# princessPhone.net
KiCad netlist of a schematic drawn in EAGLE
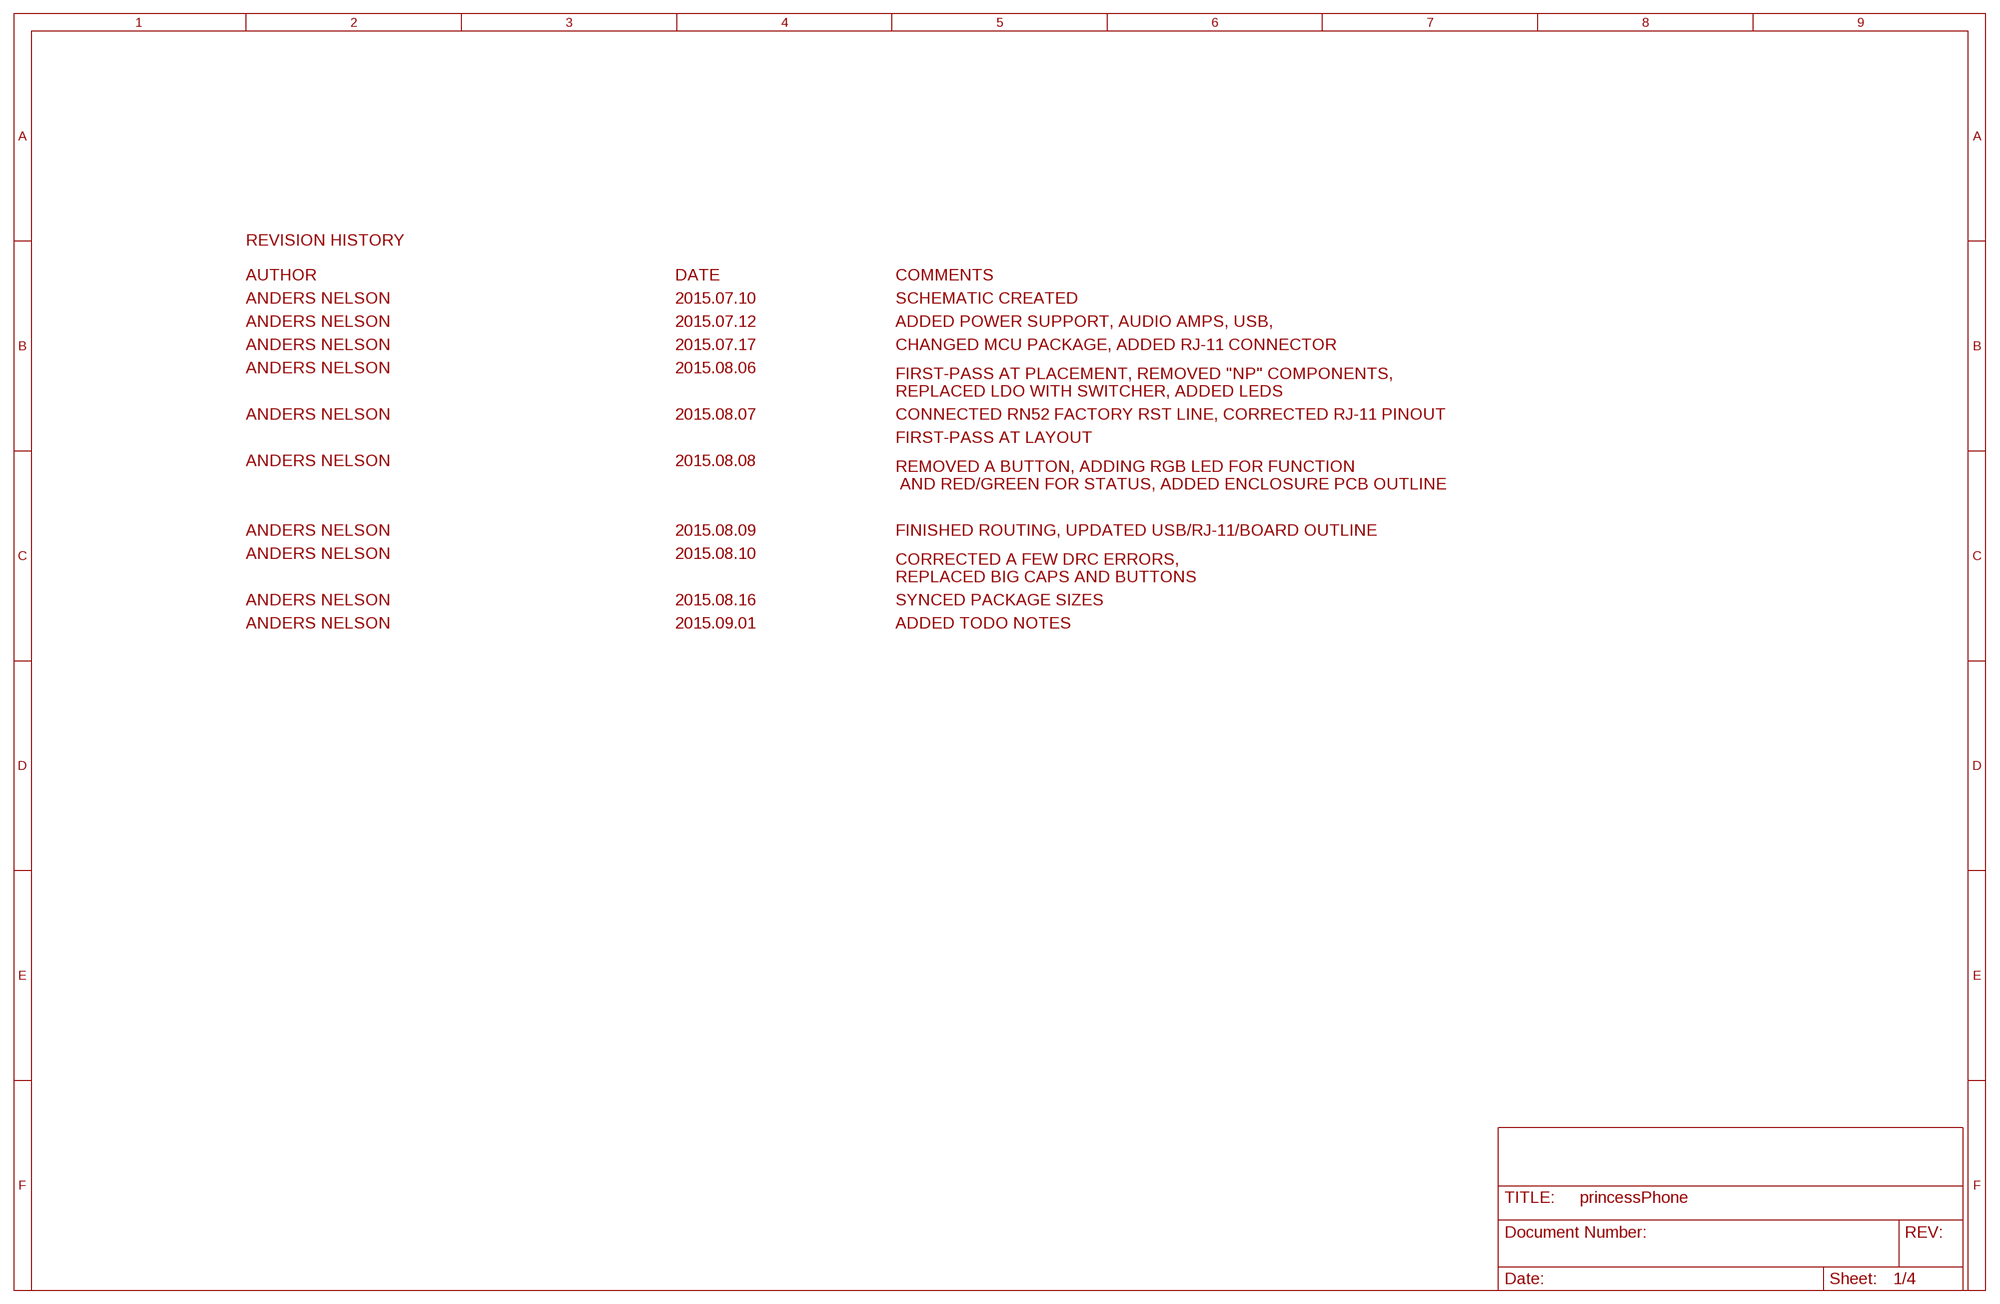
[diagram p0: schematic, sheet 1]
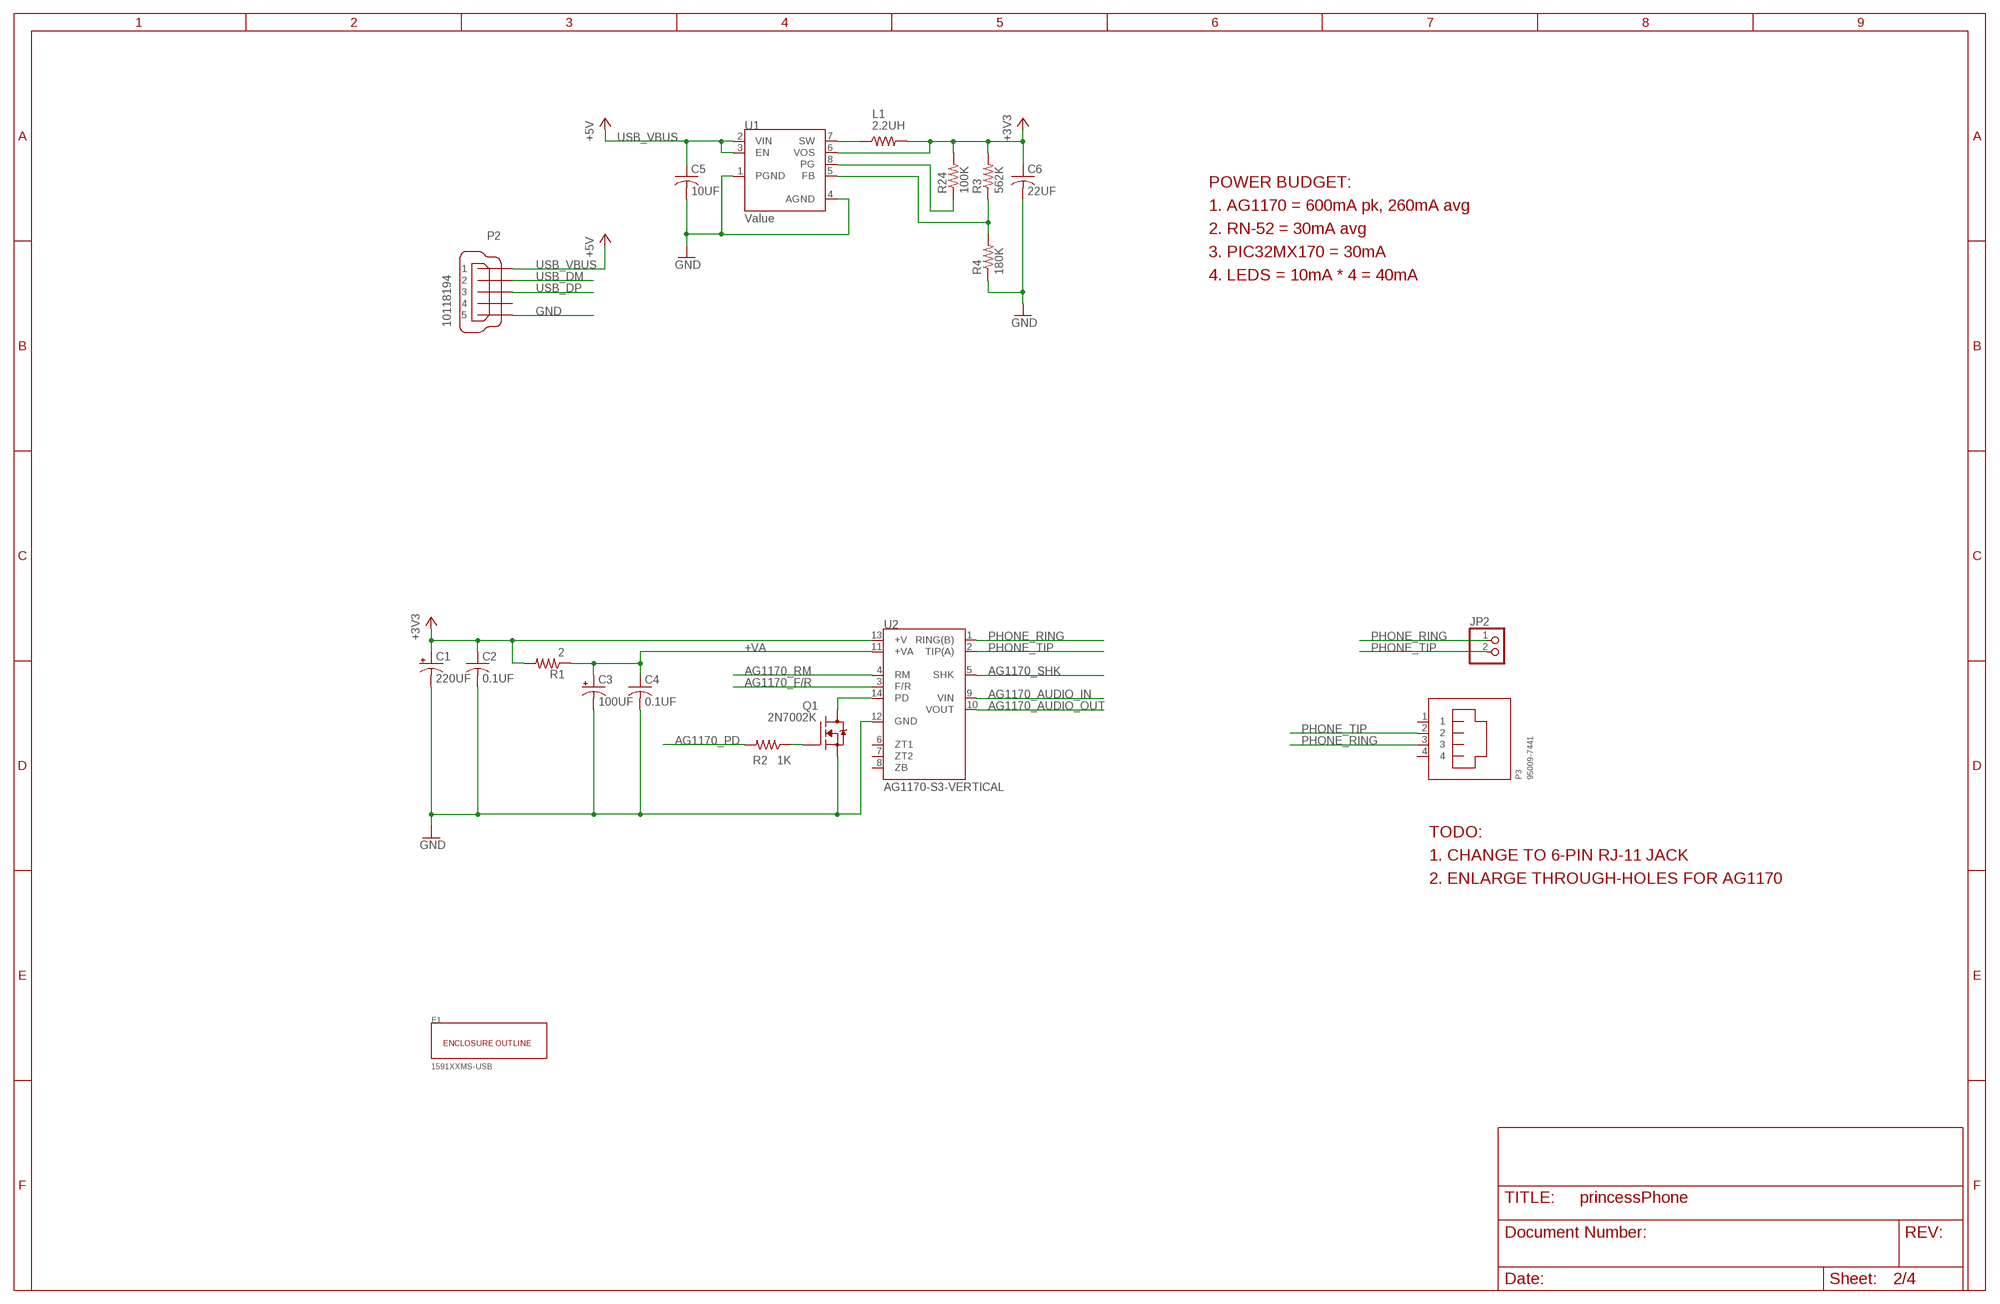
[diagram p1: schematic, sheet 2]
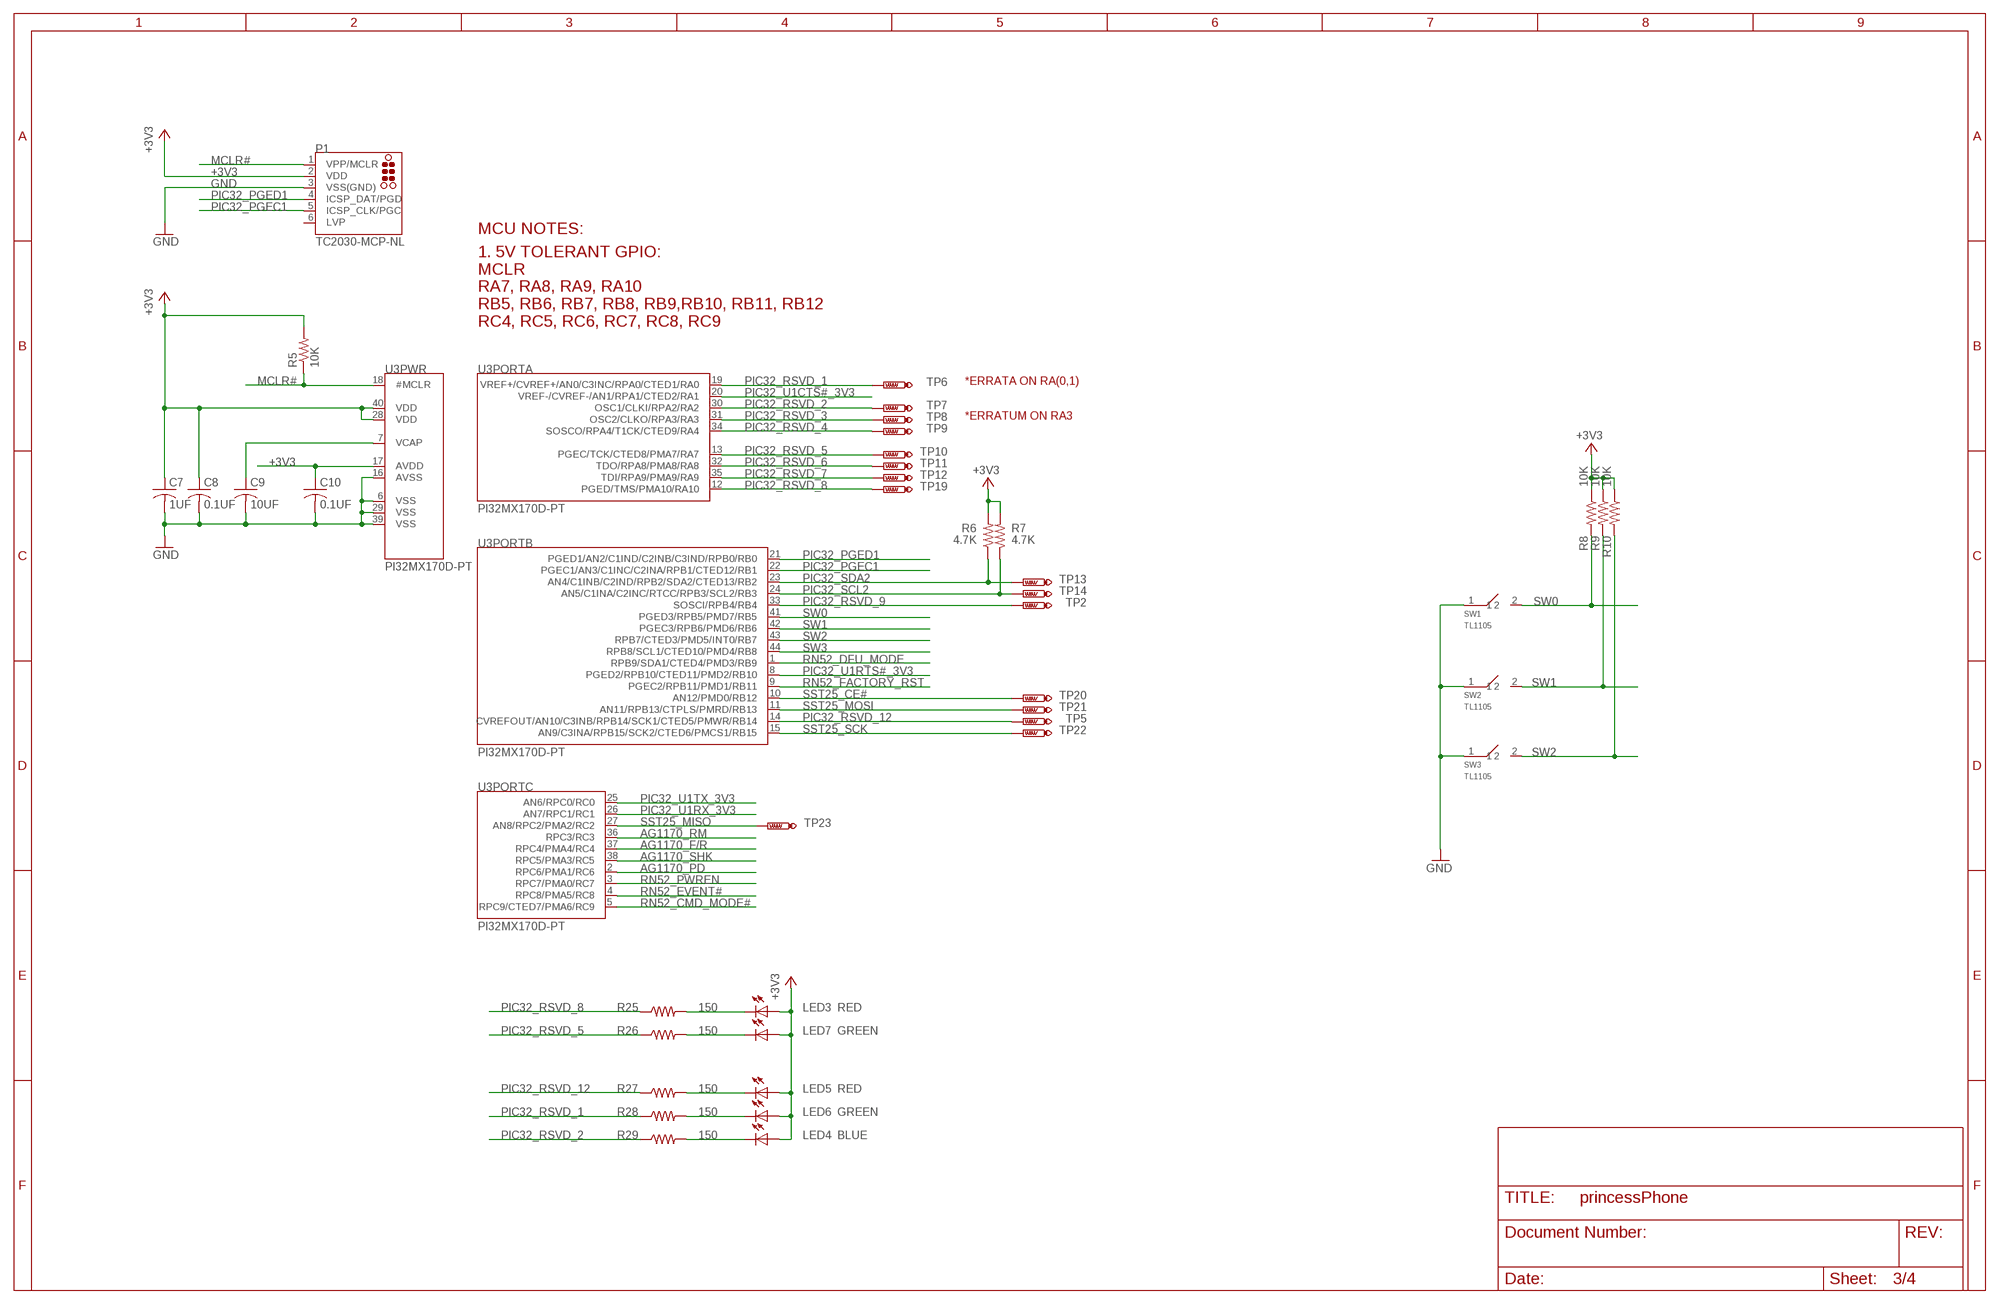
[diagram p2: schematic, sheet 3]
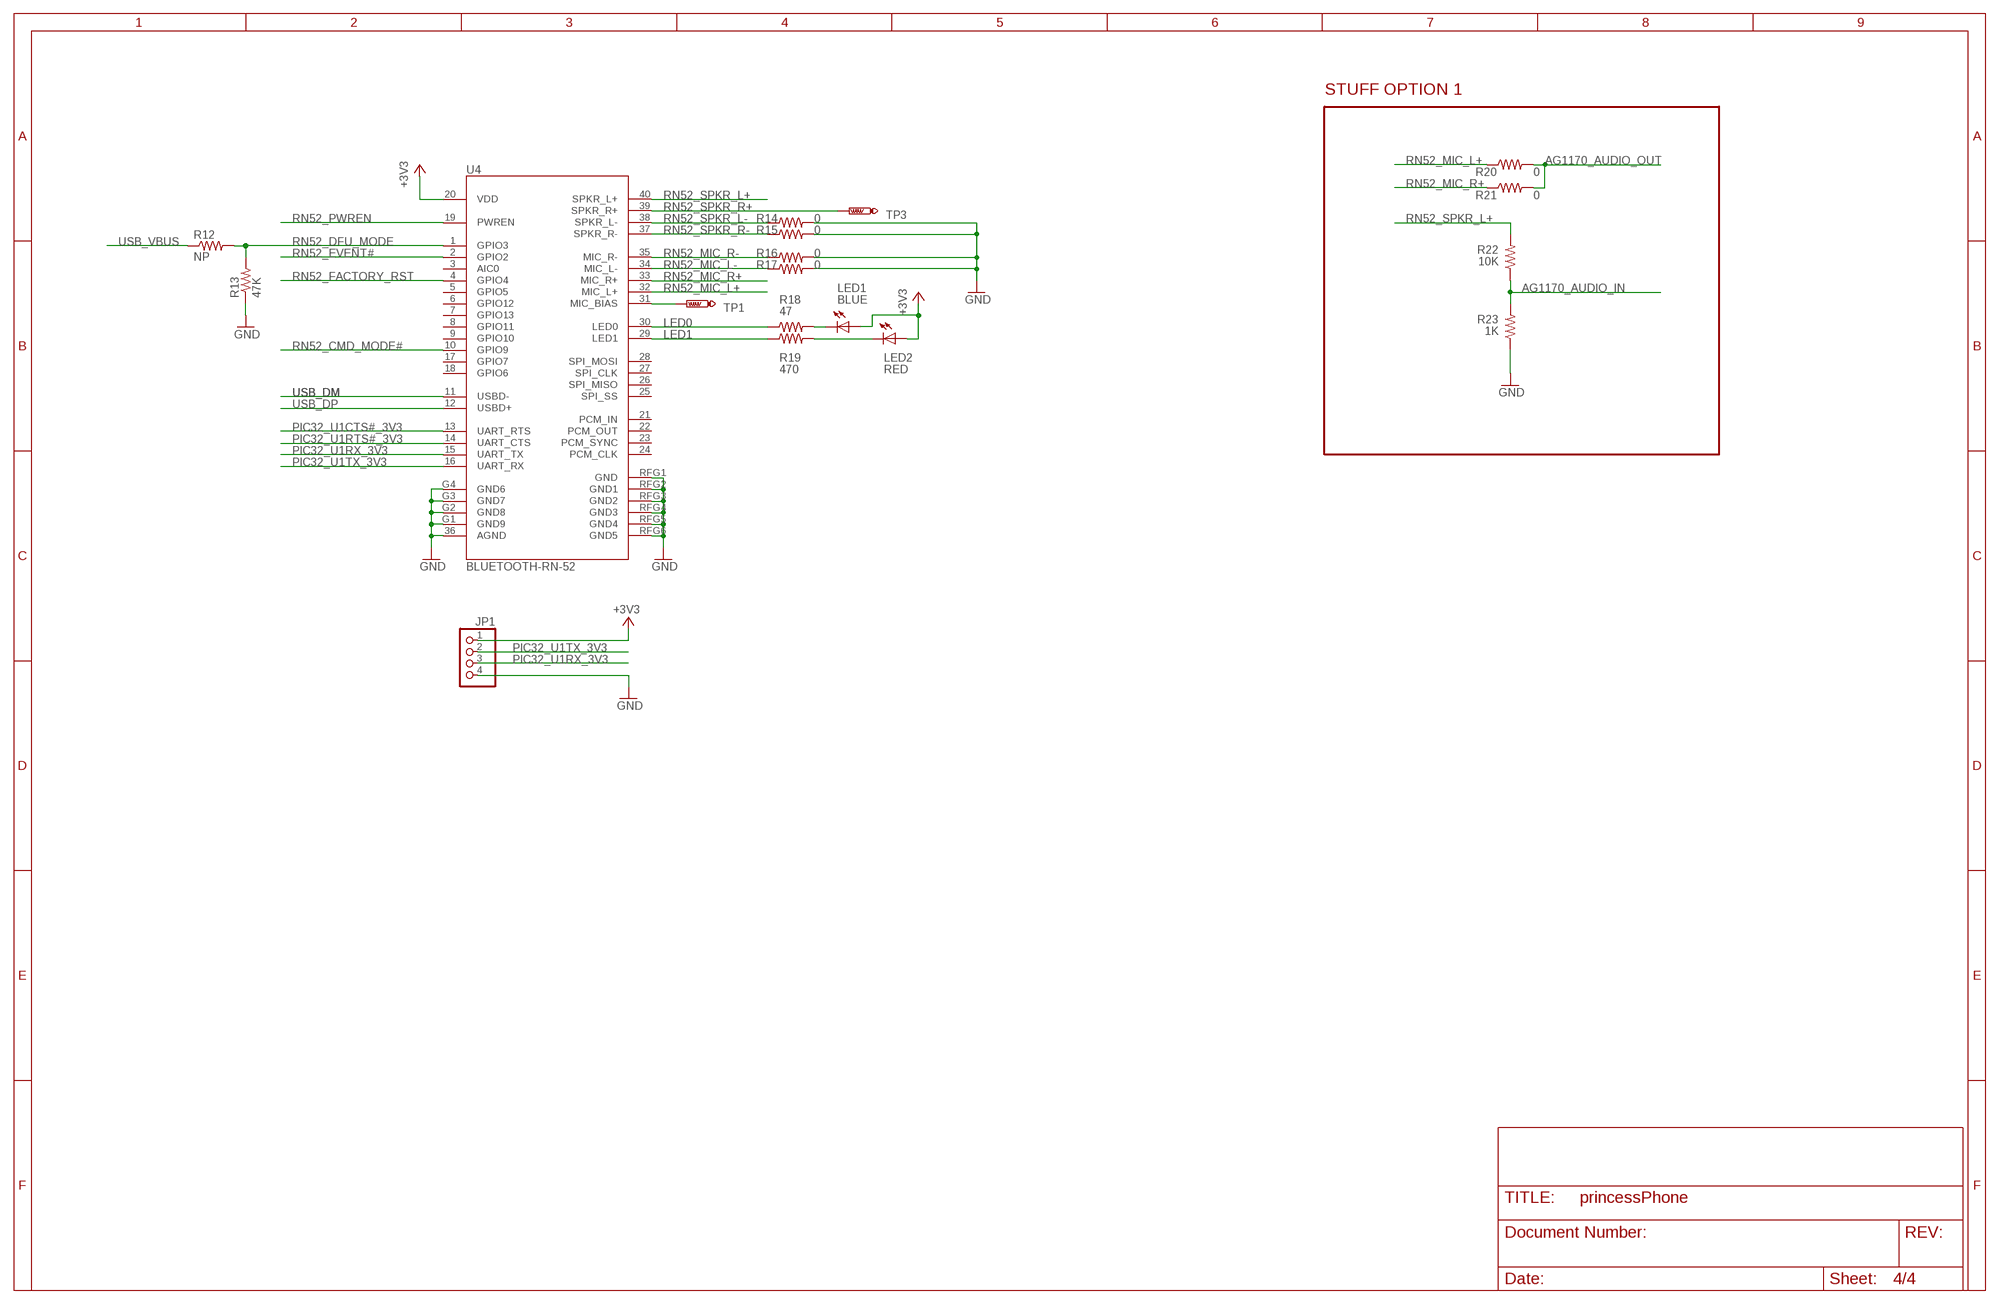
[diagram p3: schematic, sheet 4]

(export (version "E")
  (design (tool "Eeschema 10.0.6"))
  (components
    (comp (ref "C7")
      (value "1UF")
      (footprint "eagle-import:C0603")
      (libsource (lib "eagle-import") (part "C-USC0603"))
    )
    (comp (ref "C8")
      (value "0.1UF")
      (footprint "eagle-import:C0603")
      (libsource (lib "eagle-import") (part "C-USC0603"))
    )
    (comp (ref "C9")
      (value "10UF")
      (footprint "eagle-import:C0603")
      (libsource (lib "eagle-import") (part "C-USC0603"))
    )
    (comp (ref "C10")
      (value "0.1UF")
      (footprint "eagle-import:C0603")
      (libsource (lib "eagle-import") (part "C-USC0603"))
    )
    (comp (ref "LED3")
      (value "RED")
      (footprint "eagle-import:CHIPLED_0603")
      (libsource (lib "eagle-import") (part "LEDCHIPLED_0603"))
    )
    (comp (ref "LED4")
      (value "BLUE")
      (footprint "eagle-import:CHIPLED_0603")
      (libsource (lib "eagle-import") (part "LEDCHIPLED_0603"))
    )
    (comp (ref "LED5")
      (value "RED")
      (footprint "eagle-import:CHIPLED_0603")
      (libsource (lib "eagle-import") (part "LEDCHIPLED_0603"))
    )
    (comp (ref "LED6")
      (value "GREEN")
      (footprint "eagle-import:CHIPLED_0603")
      (libsource (lib "eagle-import") (part "LEDCHIPLED_0603"))
    )
    (comp (ref "LED7")
      (value "GREEN")
      (footprint "eagle-import:CHIPLED_0603")
      (libsource (lib "eagle-import") (part "LEDCHIPLED_0603"))
    )
    (comp (ref "P1")
      (value "TC2030-MCP-NL")
      (footprint "eagle-import:TC2030-MCP-NL")
      (libsource (lib "eagle-import") (part "TC2030-MCP-NL"))
    )
    (comp (ref "R5")
      (value "10K")
      (footprint "eagle-import:R0603")
      (libsource (lib "eagle-import") (part "R-US_R0603"))
    )
    (comp (ref "R6")
      (value "4.7K")
      (footprint "eagle-import:R0603")
      (libsource (lib "eagle-import") (part "R-US_R0603"))
    )
    (comp (ref "R7")
      (value "4.7K")
      (footprint "eagle-import:R0603")
      (libsource (lib "eagle-import") (part "R-US_R0603"))
    )
    (comp (ref "R8")
      (value "10K")
      (footprint "eagle-import:R0603")
      (libsource (lib "eagle-import") (part "R-US_R0603"))
    )
    (comp (ref "R9")
      (value "10K")
      (footprint "eagle-import:R0603")
      (libsource (lib "eagle-import") (part "R-US_R0603"))
    )
    (comp (ref "R10")
      (value "10K")
      (footprint "eagle-import:R0603")
      (libsource (lib "eagle-import") (part "R-US_R0603"))
    )
    (comp (ref "R25")
      (value "150")
      (footprint "eagle-import:R0603")
      (libsource (lib "eagle-import") (part "R-US_R0603"))
    )
    (comp (ref "R26")
      (value "150")
      (footprint "eagle-import:R0603")
      (libsource (lib "eagle-import") (part "R-US_R0603"))
    )
    (comp (ref "R27")
      (value "150")
      (footprint "eagle-import:R0603")
      (libsource (lib "eagle-import") (part "R-US_R0603"))
    )
    (comp (ref "R28")
      (value "150")
      (footprint "eagle-import:R0603")
      (libsource (lib "eagle-import") (part "R-US_R0603"))
    )
    (comp (ref "R29")
      (value "150")
      (footprint "eagle-import:R0603")
      (libsource (lib "eagle-import") (part "R-US_R0603"))
    )
    (comp (ref "SW1")
      (value "TL1105")
      (footprint "eagle-import:TL1105_RA")
      (libsource (lib "eagle-import") (part "TL1105"))
    )
    (comp (ref "SW2")
      (value "TL1105")
      (footprint "eagle-import:TL1105_RA")
      (libsource (lib "eagle-import") (part "TL1105"))
    )
    (comp (ref "SW3")
      (value "TL1105")
      (footprint "eagle-import:TL1105_RA")
      (libsource (lib "eagle-import") (part "TL1105"))
    )
    (comp (ref "TP2")
      (value "PTR1B1,27")
      (footprint "eagle-import:B1,27")
      (libsource (lib "eagle-import") (part "PTR1B1,27"))
    )
    (comp (ref "TP5")
      (value "PTR1B1,27")
      (footprint "eagle-import:B1,27")
      (libsource (lib "eagle-import") (part "PTR1B1,27"))
    )
    (comp (ref "TP6")
      (value "PTR1B1,27")
      (footprint "eagle-import:B1,27")
      (libsource (lib "eagle-import") (part "PTR1B1,27"))
    )
    (comp (ref "TP7")
      (value "PTR1B1,27")
      (footprint "eagle-import:B1,27")
      (libsource (lib "eagle-import") (part "PTR1B1,27"))
    )
    (comp (ref "TP8")
      (value "PTR1B1,27")
      (footprint "eagle-import:B1,27")
      (libsource (lib "eagle-import") (part "PTR1B1,27"))
    )
    (comp (ref "TP9")
      (value "PTR1B1,27")
      (footprint "eagle-import:B1,27")
      (libsource (lib "eagle-import") (part "PTR1B1,27"))
    )
    (comp (ref "TP10")
      (value "PTR1B1,27")
      (footprint "eagle-import:B1,27")
      (libsource (lib "eagle-import") (part "PTR1B1,27"))
    )
    (comp (ref "TP11")
      (value "PTR1B1,27")
      (footprint "eagle-import:B1,27")
      (libsource (lib "eagle-import") (part "PTR1B1,27"))
    )
    (comp (ref "TP12")
      (value "PTR1B1,27")
      (footprint "eagle-import:B1,27")
      (libsource (lib "eagle-import") (part "PTR1B1,27"))
    )
    (comp (ref "TP13")
      (value "PTR1B1,27")
      (footprint "eagle-import:B1,27")
      (libsource (lib "eagle-import") (part "PTR1B1,27"))
    )
    (comp (ref "TP14")
      (value "PTR1B1,27")
      (footprint "eagle-import:B1,27")
      (libsource (lib "eagle-import") (part "PTR1B1,27"))
    )
    (comp (ref "TP19")
      (value "PTR1B1,27")
      (footprint "eagle-import:B1,27")
      (libsource (lib "eagle-import") (part "PTR1B1,27"))
    )
    (comp (ref "TP20")
      (value "PTR1B1,27")
      (footprint "eagle-import:B1,27")
      (libsource (lib "eagle-import") (part "PTR1B1,27"))
    )
    (comp (ref "TP21")
      (value "PTR1B1,27")
      (footprint "eagle-import:B1,27")
      (libsource (lib "eagle-import") (part "PTR1B1,27"))
    )
    (comp (ref "TP22")
      (value "PTR1B1,27")
      (footprint "eagle-import:B1,27")
      (libsource (lib "eagle-import") (part "PTR1B1,27"))
    )
    (comp (ref "TP23")
      (value "PTR1B1,27")
      (footprint "eagle-import:B1,27")
      (libsource (lib "eagle-import") (part "PTR1B1,27"))
    )
    (comp (ref "U3")
      (value "PI32MX170D-PT")
      (footprint "eagle-import:TQFP44")
      (libsource (lib "eagle-import") (part "PI32MX1D-PT70"))
    )
    (comp (ref "C1")
      (value "220UF")
      (footprint "eagle-import:E2,5-7")
      (libsource (lib "eagle-import") (part "CPOL-USE2.5-7"))
    )
    (comp (ref "C2")
      (value "0.1UF")
      (footprint "eagle-import:C0603")
      (libsource (lib "eagle-import") (part "C-USC0603"))
    )
    (comp (ref "C3")
      (value "100UF")
      (footprint "eagle-import:E2,5-7")
      (libsource (lib "eagle-import") (part "CPOL-USE2.5-7"))
    )
    (comp (ref "C4")
      (value "0.1UF")
      (footprint "eagle-import:C0603")
      (libsource (lib "eagle-import") (part "C-USC0603"))
    )
    (comp (ref "C5")
      (value "10UF")
      (footprint "eagle-import:C0603")
      (libsource (lib "eagle-import") (part "C-USC0603"))
    )
    (comp (ref "C6")
      (value "22UF")
      (footprint "eagle-import:C1206")
      (libsource (lib "eagle-import") (part "C-USC1206"))
    )
    (comp (ref "E1")
      (value "1591XXMS-USB")
      (footprint "eagle-import:1591XXMSBK-USB")
      (libsource (lib "eagle-import") (part "1591XXMS-USB"))
    )
    (comp (ref "JP2")
      (value "PINHD-1X2")
      (footprint "eagle-import:1X02")
      (libsource (lib "eagle-import") (part "PINHD-1X2"))
    )
    (comp (ref "L1")
      (value "2.2UH")
      (footprint "eagle-import:R0805")
      (libsource (lib "eagle-import") (part "R-US_R0805"))
    )
    (comp (ref "P2")
      (value "10118194")
      (footprint "eagle-import:10118194")
      (libsource (lib "eagle-import") (part "10118194"))
    )
    (comp (ref "P3")
      (value "95009-7441")
      (footprint "eagle-import:95009-7441")
      (libsource (lib "eagle-import") (part "95009-7441"))
    )
    (comp (ref "Q1")
      (value "2N7002K")
      (footprint "eagle-import:SOT23")
      (libsource (lib "eagle-import") (part "2N7002K"))
    )
    (comp (ref "R1")
      (value "2")
      (footprint "eagle-import:R0603")
      (libsource (lib "eagle-import") (part "R-US_R0603"))
    )
    (comp (ref "R2")
      (value "1K")
      (footprint "eagle-import:R0603")
      (libsource (lib "eagle-import") (part "R-US_R0603"))
    )
    (comp (ref "R3")
      (value "562K")
      (footprint "eagle-import:R0603")
      (libsource (lib "eagle-import") (part "R-US_R0603"))
    )
    (comp (ref "R4")
      (value "180K")
      (footprint "eagle-import:R0603")
      (libsource (lib "eagle-import") (part "R-US_R0603"))
    )
    (comp (ref "R24")
      (value "100K")
      (footprint "eagle-import:R0603")
      (libsource (lib "eagle-import") (part "R-US_R0603"))
    )
    (comp (ref "U1")
      (value "Value")
      (footprint "eagle-import:DGK0008A_N")
      (fields
        (field (name "ALTERNATEPARTNUMBER") "TPS62160DGKT")
        (field (name "MANUFACTURER") "Texas Instruments")
        (field (name "PARTNUMBER") "TPS62160DGKR")
      )
      (libsource (lib "eagle-import") (part "TPS62160DGKR"))
    )
    (comp (ref "U2")
      (value "AG1170-S3-VERTICAL")
      (footprint "eagle-import:AG1170X-S")
      (libsource (lib "eagle-import") (part "AG1170-VERTICAL-S3"))
    )
    (comp (ref "JP1")
      (value "PINHD-1X4")
      (footprint "eagle-import:1X04")
      (libsource (lib "eagle-import") (part "PINHD-1X4"))
    )
    (comp (ref "LED1")
      (value "BLUE")
      (footprint "eagle-import:CHIPLED_0603")
      (libsource (lib "eagle-import") (part "LEDCHIPLED_0603"))
    )
    (comp (ref "LED2")
      (value "RED")
      (footprint "eagle-import:CHIPLED_0603")
      (libsource (lib "eagle-import") (part "LEDCHIPLED_0603"))
    )
    (comp (ref "R12")
      (value "NP")
      (footprint "eagle-import:R0603")
      (libsource (lib "eagle-import") (part "R-US_R0603"))
    )
    (comp (ref "R13")
      (value "47K")
      (footprint "eagle-import:R0603")
      (libsource (lib "eagle-import") (part "R-US_R0603"))
    )
    (comp (ref "R14")
      (value "0")
      (footprint "eagle-import:R0603")
      (libsource (lib "eagle-import") (part "R-US_R0603"))
    )
    (comp (ref "R15")
      (value "0")
      (footprint "eagle-import:R0603")
      (libsource (lib "eagle-import") (part "R-US_R0603"))
    )
    (comp (ref "R16")
      (value "0")
      (footprint "eagle-import:R0603")
      (libsource (lib "eagle-import") (part "R-US_R0603"))
    )
    (comp (ref "R17")
      (value "0")
      (footprint "eagle-import:R0603")
      (libsource (lib "eagle-import") (part "R-US_R0603"))
    )
    (comp (ref "R18")
      (value "47")
      (footprint "eagle-import:R0603")
      (libsource (lib "eagle-import") (part "R-US_R0603"))
    )
    (comp (ref "R19")
      (value "470")
      (footprint "eagle-import:R0603")
      (libsource (lib "eagle-import") (part "R-US_R0603"))
    )
    (comp (ref "R20")
      (value "0")
      (footprint "eagle-import:R0603")
      (libsource (lib "eagle-import") (part "R-US_R0603"))
    )
    (comp (ref "R21")
      (value "0")
      (footprint "eagle-import:R0603")
      (libsource (lib "eagle-import") (part "R-US_R0603"))
    )
    (comp (ref "R22")
      (value "10K")
      (footprint "eagle-import:R0603")
      (libsource (lib "eagle-import") (part "R-US_R0603"))
    )
    (comp (ref "R23")
      (value "1K")
      (footprint "eagle-import:R0603")
      (libsource (lib "eagle-import") (part "R-US_R0603"))
    )
    (comp (ref "TP1")
      (value "PTR1B1,27")
      (footprint "eagle-import:B1,27")
      (libsource (lib "eagle-import") (part "PTR1B1,27"))
    )
    (comp (ref "TP3")
      (value "PTR1B1,27")
      (footprint "eagle-import:B1,27")
      (libsource (lib "eagle-import") (part "PTR1B1,27"))
    )
    (comp (ref "U4")
      (value "BLUETOOTH-RN-52")
      (footprint "eagle-import:RN-52")
      (libsource (lib "eagle-import") (part "BLUETOOTH-RN-52"))
    )
  )
  (nets
    (net (code "1") (name "+3V3") (class "Default")
      (node (ref "C1") (pin "+") (pinfunction "+_+") (pintype "passive"))
      (node (ref "C10") (pin "1") (pinfunction "1_1") (pintype "passive"))
      (node (ref "C2") (pin "1") (pinfunction "1_1") (pintype "passive"))
      (node (ref "C6") (pin "1") (pinfunction "1_1") (pintype "passive"))
      (node (ref "C7") (pin "1") (pinfunction "1_1") (pintype "passive"))
      (node (ref "C8") (pin "1") (pinfunction "1_1") (pintype "passive"))
      (node (ref "JP1") (pin "1") (pinfunction "1_1") (pintype "passive"))
      (node (ref "L1") (pin "2") (pinfunction "2_2") (pintype "passive"))
      (node (ref "LED1") (pin "A") (pinfunction "A_A") (pintype "passive"))
      (node (ref "LED2") (pin "A") (pinfunction "A_A") (pintype "passive"))
      (node (ref "LED3") (pin "A") (pinfunction "A_A") (pintype "passive"))
      (node (ref "LED4") (pin "A") (pinfunction "A_A") (pintype "passive"))
      (node (ref "LED5") (pin "A") (pinfunction "A_A") (pintype "passive"))
      (node (ref "LED6") (pin "A") (pinfunction "A_A") (pintype "passive"))
      (node (ref "LED7") (pin "A") (pinfunction "A_A") (pintype "passive"))
      (node (ref "P1") (pin "2") (pinfunction "VDD_2") (pintype "power_in"))
      (node (ref "R1") (pin "2") (pinfunction "2_2") (pintype "passive"))
      (node (ref "R10") (pin "1") (pinfunction "1_1") (pintype "passive"))
      (node (ref "R24") (pin "2") (pinfunction "2_2") (pintype "passive"))
      (node (ref "R3") (pin "2") (pinfunction "2_2") (pintype "passive"))
      (node (ref "R5") (pin "2") (pinfunction "2_2") (pintype "passive"))
      (node (ref "R6") (pin "2") (pinfunction "2_2") (pintype "passive"))
      (node (ref "R7") (pin "2") (pinfunction "2_2") (pintype "passive"))
      (node (ref "R8") (pin "1") (pinfunction "1_1") (pintype "passive"))
      (node (ref "R9") (pin "1") (pinfunction "1_1") (pintype "passive"))
      (node (ref "U1") (pin "6") (pinfunction "VOS_6") (pintype "input"))
      (node (ref "U2") (pin "13") (pinfunction "+V_13") (pintype "bidirectional"))
      (node (ref "U3") (pin "17") (pinfunction "AVDD_17") (pintype "bidirectional"))
      (node (ref "U3") (pin "28") (pinfunction "VDD_28") (pintype "bidirectional"))
      (node (ref "U3") (pin "40") (pinfunction "VDD_40") (pintype "bidirectional"))
      (node (ref "U4") (pin "20") (pinfunction "VDD_20") (pintype "bidirectional"))
    )
    (net (code "2") (name "+VA") (class "Default")
      (node (ref "C3") (pin "+") (pinfunction "+_+") (pintype "passive"))
      (node (ref "C4") (pin "1") (pinfunction "1_1") (pintype "passive"))
      (node (ref "R1") (pin "1") (pinfunction "1_1") (pintype "passive"))
      (node (ref "U2") (pin "11") (pinfunction "+VA_11") (pintype "bidirectional"))
    )
    (net (code "3") (name "AG1170_AUDIO_IN") (class "Default")
      (node (ref "R22") (pin "1") (pinfunction "1_1") (pintype "passive"))
      (node (ref "R23") (pin "2") (pinfunction "2_2") (pintype "passive"))
      (node (ref "U2") (pin "9") (pinfunction "VIN_9") (pintype "bidirectional"))
    )
    (net (code "4") (name "AG1170_AUDIO_OUT") (class "Default")
      (node (ref "R20") (pin "2") (pinfunction "2_2") (pintype "passive"))
      (node (ref "R21") (pin "2") (pinfunction "2_2") (pintype "passive"))
      (node (ref "U2") (pin "10") (pinfunction "VOUT_10") (pintype "bidirectional"))
    )
    (net (code "5") (name "AG1170_F{slash}R") (class "Default")
      (node (ref "U2") (pin "3") (pinfunction "F/R_3") (pintype "bidirectional"))
      (node (ref "U3") (pin "37") (pinfunction "RPC4/PMA4/RC4_37") (pintype "bidirectional"))
    )
    (net (code "6") (name "AG1170_PD") (class "Default")
      (node (ref "R2") (pin "2") (pinfunction "2_2") (pintype "passive"))
      (node (ref "U3") (pin "2") (pinfunction "RPC6/PMA1/RC6_2") (pintype "bidirectional"))
    )
    (net (code "7") (name "AG1170_RM") (class "Default")
      (node (ref "U2") (pin "4") (pinfunction "RM_4") (pintype "bidirectional"))
      (node (ref "U3") (pin "36") (pinfunction "RPC3/RC3_36") (pintype "bidirectional"))
    )
    (net (code "8") (name "AG1170_SHK") (class "Default")
      (node (ref "U2") (pin "5") (pinfunction "SHK_5") (pintype "bidirectional"))
      (node (ref "U3") (pin "38") (pinfunction "RPC5/PMA3/RC5_38") (pintype "bidirectional"))
    )
    (net (code "9") (name "GND") (class "Default")
      (node (ref "C1") (pin "-") (pinfunction "-_-") (pintype "passive"))
      (node (ref "C10") (pin "2") (pinfunction "2_2") (pintype "passive"))
      (node (ref "C2") (pin "2") (pinfunction "2_2") (pintype "passive"))
      (node (ref "C3") (pin "-") (pinfunction "-_-") (pintype "passive"))
      (node (ref "C4") (pin "2") (pinfunction "2_2") (pintype "passive"))
      (node (ref "C5") (pin "2") (pinfunction "2_2") (pintype "passive"))
      (node (ref "C6") (pin "2") (pinfunction "2_2") (pintype "passive"))
      (node (ref "C7") (pin "2") (pinfunction "2_2") (pintype "passive"))
      (node (ref "C8") (pin "2") (pinfunction "2_2") (pintype "passive"))
      (node (ref "C9") (pin "2") (pinfunction "2_2") (pintype "passive"))
      (node (ref "JP1") (pin "4") (pinfunction "4_4") (pintype "passive"))
      (node (ref "P1") (pin "3") (pinfunction "VSS(GND)_3") (pintype "power_in"))
      (node (ref "P2") (pin "5") (pinfunction "5_5") (pintype "input"))
      (node (ref "Q1") (pin "2") (pinfunction "S_2") (pintype "passive"))
      (node (ref "R13") (pin "1") (pinfunction "1_1") (pintype "passive"))
      (node (ref "R14") (pin "2") (pinfunction "2_2") (pintype "passive"))
      (node (ref "R15") (pin "2") (pinfunction "2_2") (pintype "passive"))
      (node (ref "R16") (pin "2") (pinfunction "2_2") (pintype "passive"))
      (node (ref "R17") (pin "2") (pinfunction "2_2") (pintype "passive"))
      (node (ref "R23") (pin "1") (pinfunction "1_1") (pintype "passive"))
      (node (ref "R4") (pin "1") (pinfunction "1_1") (pintype "passive"))
      (node (ref "SW1") (pin "1") (pinfunction "1_1") (pintype "bidirectional"))
      (node (ref "SW2") (pin "1") (pinfunction "1_1") (pintype "bidirectional"))
      (node (ref "SW3") (pin "1") (pinfunction "1_1") (pintype "bidirectional"))
      (node (ref "U1") (pin "1") (pinfunction "PGND_1") (pintype "power_in"))
      (node (ref "U1") (pin "4") (pinfunction "AGND_4") (pintype "power_in"))
      (node (ref "U2") (pin "12") (pinfunction "GND_12") (pintype "bidirectional"))
      (node (ref "U3") (pin "16") (pinfunction "AVSS_16") (pintype "bidirectional"))
      (node (ref "U3") (pin "29") (pinfunction "VSS_29") (pintype "bidirectional"))
      (node (ref "U3") (pin "39") (pinfunction "VSS_39") (pintype "bidirectional"))
      (node (ref "U3") (pin "6") (pinfunction "VSS_6") (pintype "bidirectional"))
      (node (ref "U4") (pin "36") (pinfunction "AGND_36") (pintype "bidirectional"))
      (node (ref "U4") (pin "G1") (pinfunction "GND9_G1") (pintype "bidirectional"))
      (node (ref "U4") (pin "G2") (pinfunction "GND8_G2") (pintype "bidirectional"))
      (node (ref "U4") (pin "G3") (pinfunction "GND7_G3") (pintype "bidirectional"))
      (node (ref "U4") (pin "G4") (pinfunction "GND6_G4") (pintype "bidirectional"))
      (node (ref "U4") (pin "RFG1") (pinfunction "GND_RFG1") (pintype "bidirectional"))
      (node (ref "U4") (pin "RFG2") (pinfunction "GND1_RFG2") (pintype "bidirectional"))
      (node (ref "U4") (pin "RFG3") (pinfunction "GND2_RFG3") (pintype "bidirectional"))
      (node (ref "U4") (pin "RFG4") (pinfunction "GND3_RFG4") (pintype "bidirectional"))
      (node (ref "U4") (pin "RFG5") (pinfunction "GND4_RFG5") (pintype "bidirectional"))
      (node (ref "U4") (pin "RFG6") (pinfunction "GND5_RFG6") (pintype "bidirectional"))
    )
    (net (code "10") (name "LED0") (class "Default")
      (node (ref "R18") (pin "1") (pinfunction "1_1") (pintype "passive"))
      (node (ref "U4") (pin "30") (pinfunction "LED0_30") (pintype "bidirectional"))
    )
    (net (code "11") (name "LED1") (class "Default")
      (node (ref "R19") (pin "1") (pinfunction "1_1") (pintype "passive"))
      (node (ref "U4") (pin "29") (pinfunction "LED1_29") (pintype "bidirectional"))
    )
    (net (code "12") (name "MCLR#") (class "Default")
      (node (ref "P1") (pin "1") (pinfunction "VPP/MCLR_1") (pintype "passive"))
      (node (ref "R5") (pin "1") (pinfunction "1_1") (pintype "passive"))
      (node (ref "U3") (pin "18") (pinfunction "#MCLR_18") (pintype "bidirectional"))
    )
    (net (code "13") (name "Net-(LED1-PadC)") (class "Default")
      (node (ref "LED1") (pin "C") (pinfunction "C_C") (pintype "passive"))
      (node (ref "R18") (pin "2") (pinfunction "2_2") (pintype "passive"))
    )
    (net (code "14") (name "Net-(LED2-PadC)") (class "Default")
      (node (ref "LED2") (pin "C") (pinfunction "C_C") (pintype "passive"))
      (node (ref "R19") (pin "2") (pinfunction "2_2") (pintype "passive"))
    )
    (net (code "15") (name "Net-(LED3-PadC)") (class "Default")
      (node (ref "LED3") (pin "C") (pinfunction "C_C") (pintype "passive"))
      (node (ref "R25") (pin "2") (pinfunction "2_2") (pintype "passive"))
    )
    (net (code "16") (name "Net-(LED4-PadC)") (class "Default")
      (node (ref "LED4") (pin "C") (pinfunction "C_C") (pintype "passive"))
      (node (ref "R29") (pin "2") (pinfunction "2_2") (pintype "passive"))
    )
    (net (code "17") (name "Net-(LED5-PadC)") (class "Default")
      (node (ref "LED5") (pin "C") (pinfunction "C_C") (pintype "passive"))
      (node (ref "R27") (pin "2") (pinfunction "2_2") (pintype "passive"))
    )
    (net (code "18") (name "Net-(LED6-PadC)") (class "Default")
      (node (ref "LED6") (pin "C") (pinfunction "C_C") (pintype "passive"))
      (node (ref "R28") (pin "2") (pinfunction "2_2") (pintype "passive"))
    )
    (net (code "19") (name "Net-(LED7-PadC)") (class "Default")
      (node (ref "LED7") (pin "C") (pinfunction "C_C") (pintype "passive"))
      (node (ref "R26") (pin "2") (pinfunction "2_2") (pintype "passive"))
    )
    (net (code "20") (name "Net-(Q1-D)") (class "Default")
      (node (ref "Q1") (pin "3") (pinfunction "D_3") (pintype "passive"))
      (node (ref "U2") (pin "14") (pinfunction "PD_14") (pintype "bidirectional"))
    )
    (net (code "21") (name "Net-(Q1-G)") (class "Default")
      (node (ref "Q1") (pin "1") (pinfunction "G_1") (pintype "passive"))
      (node (ref "R2") (pin "1") (pinfunction "1_1") (pintype "passive"))
    )
    (net (code "22") (name "Net-(U1-FB)") (class "Default")
      (node (ref "R3") (pin "1") (pinfunction "1_1") (pintype "passive"))
      (node (ref "R4") (pin "2") (pinfunction "2_2") (pintype "passive"))
      (node (ref "U1") (pin "5") (pinfunction "FB_5") (pintype "input"))
    )
    (net (code "23") (name "Net-(U1-PG)") (class "Default")
      (node (ref "R24") (pin "1") (pinfunction "1_1") (pintype "passive"))
      (node (ref "U1") (pin "8") (pinfunction "PG_8") (pintype "tri_state"))
    )
    (net (code "24") (name "Net-(U1-SW)") (class "Default")
      (node (ref "L1") (pin "1") (pinfunction "1_1") (pintype "passive"))
      (node (ref "U1") (pin "7") (pinfunction "SW_7") (pintype "power_in"))
    )
    (net (code "25") (name "Net-(U3D-VCAP)") (class "Default")
      (node (ref "C9") (pin "1") (pinfunction "1_1") (pintype "passive"))
      (node (ref "U3") (pin "7") (pinfunction "VCAP_7") (pintype "bidirectional"))
    )
    (net (code "26") (name "Net-(U4-MIC_BIAS)") (class "Default")
      (node (ref "TP1") (pin "TP") (pinfunction "TP_TP") (pintype "input"))
      (node (ref "U4") (pin "31") (pinfunction "MIC_BIAS_31") (pintype "bidirectional"))
    )
    (net (code "27") (name "PHONE_RING") (class "Default")
      (node (ref "JP2") (pin "1") (pinfunction "1_1") (pintype "passive"))
      (node (ref "P3") (pin "3") (pinfunction "3_3") (pintype "bidirectional"))
      (node (ref "U2") (pin "1") (pinfunction "RING(B)_1") (pintype "bidirectional"))
    )
    (net (code "28") (name "PHONE_TIP") (class "Default")
      (node (ref "JP2") (pin "2") (pinfunction "2_2") (pintype "passive"))
      (node (ref "P3") (pin "2") (pinfunction "2_2") (pintype "bidirectional"))
      (node (ref "U2") (pin "2") (pinfunction "TIP(A)_2") (pintype "bidirectional"))
    )
    (net (code "29") (name "PIC32_PGEC1") (class "Default")
      (node (ref "P1") (pin "5") (pinfunction "ICSP_CLK/PGC_5") (pintype "output"))
      (node (ref "U3") (pin "22") (pinfunction "PGEC1/AN3/C1INC/C2INA/RPB1/CTED12/RB1_22") (pintype "bidirectional"))
    )
    (net (code "30") (name "PIC32_PGED1") (class "Default")
      (node (ref "P1") (pin "4") (pinfunction "ICSP_DAT/PGD_4") (pintype "bidirectional"))
      (node (ref "U3") (pin "21") (pinfunction "PGED1/AN2/C1IND/C2INB/C3IND/RPB0/RB0_21") (pintype "bidirectional"))
    )
    (net (code "31") (name "PIC32_RSVD_1") (class "Default")
      (node (ref "R28") (pin "1") (pinfunction "1_1") (pintype "passive"))
      (node (ref "TP6") (pin "TP") (pinfunction "TP_TP") (pintype "input"))
      (node (ref "U3") (pin "19") (pinfunction "VREF+/CVREF+/AN0/C3INC/RPA0/CTED1/RA0_19") (pintype "bidirectional"))
    )
    (net (code "32") (name "PIC32_RSVD_2") (class "Default")
      (node (ref "R29") (pin "1") (pinfunction "1_1") (pintype "passive"))
      (node (ref "TP7") (pin "TP") (pinfunction "TP_TP") (pintype "input"))
      (node (ref "U3") (pin "30") (pinfunction "OSC1/CLKI/RPA2/RA2_30") (pintype "bidirectional"))
    )
    (net (code "33") (name "PIC32_RSVD_3") (class "Default")
      (node (ref "TP8") (pin "TP") (pinfunction "TP_TP") (pintype "input"))
      (node (ref "U3") (pin "31") (pinfunction "OSC2/CLKO/RPA3/RA3_31") (pintype "bidirectional"))
    )
    (net (code "34") (name "PIC32_RSVD_4") (class "Default")
      (node (ref "TP9") (pin "TP") (pinfunction "TP_TP") (pintype "input"))
      (node (ref "U3") (pin "34") (pinfunction "SOSCO/RPA4/T1CK/CTED9/RA4_34") (pintype "bidirectional"))
    )
    (net (code "35") (name "PIC32_RSVD_5") (class "Default")
      (node (ref "R26") (pin "1") (pinfunction "1_1") (pintype "passive"))
      (node (ref "TP10") (pin "TP") (pinfunction "TP_TP") (pintype "input"))
      (node (ref "U3") (pin "13") (pinfunction "PGEC/TCK/CTED8/PMA7/RA7_13") (pintype "bidirectional"))
    )
    (net (code "36") (name "PIC32_RSVD_6") (class "Default")
      (node (ref "TP11") (pin "TP") (pinfunction "TP_TP") (pintype "input"))
      (node (ref "U3") (pin "32") (pinfunction "TDO/RPA8/PMA8/RA8_32") (pintype "bidirectional"))
    )
    (net (code "37") (name "PIC32_RSVD_7") (class "Default")
      (node (ref "TP12") (pin "TP") (pinfunction "TP_TP") (pintype "input"))
      (node (ref "U3") (pin "35") (pinfunction "TDI/RPA9/PMA9/RA9_35") (pintype "bidirectional"))
    )
    (net (code "38") (name "PIC32_RSVD_8") (class "Default")
      (node (ref "R25") (pin "1") (pinfunction "1_1") (pintype "passive"))
      (node (ref "TP19") (pin "TP") (pinfunction "TP_TP") (pintype "input"))
      (node (ref "U3") (pin "12") (pinfunction "PGED/TMS/PMA10/RA10_12") (pintype "bidirectional"))
    )
    (net (code "39") (name "PIC32_RSVD_9") (class "Default")
      (node (ref "TP2") (pin "TP") (pinfunction "TP_TP") (pintype "input"))
      (node (ref "U3") (pin "33") (pinfunction "SOSCI/RPB4/RB4_33") (pintype "bidirectional"))
    )
    (net (code "40") (name "PIC32_RSVD_12") (class "Default")
      (node (ref "R27") (pin "1") (pinfunction "1_1") (pintype "passive"))
      (node (ref "TP5") (pin "TP") (pinfunction "TP_TP") (pintype "input"))
      (node (ref "U3") (pin "14") (pinfunction "CVREFOUT/AN10/C3INB/RPB14/SCK1/CTED5/PMWR/RB14_14") (pintype "bidirectional"))
    )
    (net (code "41") (name "PIC32_SCL2") (class "Default")
      (node (ref "R7") (pin "1") (pinfunction "1_1") (pintype "passive"))
      (node (ref "TP14") (pin "TP") (pinfunction "TP_TP") (pintype "input"))
      (node (ref "U3") (pin "24") (pinfunction "AN5/C1INA/C2INC/RTCC/RPB3/SCL2/RB3_24") (pintype "bidirectional"))
    )
    (net (code "42") (name "PIC32_SDA2") (class "Default")
      (node (ref "R6") (pin "1") (pinfunction "1_1") (pintype "passive"))
      (node (ref "TP13") (pin "TP") (pinfunction "TP_TP") (pintype "input"))
      (node (ref "U3") (pin "23") (pinfunction "AN4/C1INB/C2IND/RPB2/SDA2/CTED13/RB2_23") (pintype "bidirectional"))
    )
    (net (code "43") (name "PIC32_U1CTS#_3V3") (class "Default")
      (node (ref "U3") (pin "20") (pinfunction "VREF-/CVREF-/AN1/RPA1/CTED2/RA1_20") (pintype "bidirectional"))
      (node (ref "U4") (pin "13") (pinfunction "UART_RTS_13") (pintype "bidirectional"))
    )
    (net (code "44") (name "PIC32_U1RTS#_3V3") (class "Default")
      (node (ref "U3") (pin "8") (pinfunction "PGED2/RPB10/CTED11/PMD2/RB10_8") (pintype "bidirectional"))
      (node (ref "U4") (pin "14") (pinfunction "UART_CTS_14") (pintype "bidirectional"))
    )
    (net (code "45") (name "PIC32_U1RX_3V3") (class "Default")
      (node (ref "JP1") (pin "3") (pinfunction "3_3") (pintype "passive"))
      (node (ref "U3") (pin "26") (pinfunction "AN7/RPC1/RC1_26") (pintype "bidirectional"))
      (node (ref "U4") (pin "15") (pinfunction "UART_TX_15") (pintype "bidirectional"))
    )
    (net (code "46") (name "PIC32_U1TX_3V3") (class "Default")
      (node (ref "JP1") (pin "2") (pinfunction "2_2") (pintype "passive"))
      (node (ref "U3") (pin "25") (pinfunction "AN6/RPC0/RC0_25") (pintype "bidirectional"))
      (node (ref "U4") (pin "16") (pinfunction "UART_RX_16") (pintype "bidirectional"))
    )
    (net (code "47") (name "RN52_CMD_MODE#") (class "Default")
      (node (ref "U3") (pin "5") (pinfunction "RPC9/CTED7/PMA6/RC9_5") (pintype "bidirectional"))
      (node (ref "U4") (pin "10") (pinfunction "GPIO9_10") (pintype "bidirectional"))
    )
    (net (code "48") (name "RN52_DFU_MODE") (class "Default")
      (node (ref "R12") (pin "2") (pinfunction "2_2") (pintype "passive"))
      (node (ref "R13") (pin "2") (pinfunction "2_2") (pintype "passive"))
      (node (ref "U3") (pin "1") (pinfunction "RPB9/SDA1/CTED4/PMD3/RB9_1") (pintype "bidirectional"))
      (node (ref "U4") (pin "1") (pinfunction "GPIO3_1") (pintype "bidirectional"))
    )
    (net (code "49") (name "RN52_EVENT#") (class "Default")
      (node (ref "U3") (pin "4") (pinfunction "RPC8/PMA5/RC8_4") (pintype "bidirectional"))
      (node (ref "U4") (pin "2") (pinfunction "GPIO2_2") (pintype "bidirectional"))
    )
    (net (code "50") (name "RN52_FACTORY_RST") (class "Default")
      (node (ref "U3") (pin "9") (pinfunction "PGEC2/RPB11/PMD1/RB11_9") (pintype "bidirectional"))
      (node (ref "U4") (pin "4") (pinfunction "GPIO4_4") (pintype "bidirectional"))
    )
    (net (code "51") (name "RN52_MIC_L+") (class "Default")
      (node (ref "R20") (pin "1") (pinfunction "1_1") (pintype "passive"))
      (node (ref "U4") (pin "32") (pinfunction "MIC_L+_32") (pintype "bidirectional"))
    )
    (net (code "52") (name "RN52_MIC_L-") (class "Default")
      (node (ref "R17") (pin "1") (pinfunction "1_1") (pintype "passive"))
      (node (ref "U4") (pin "34") (pinfunction "MIC_L-_34") (pintype "bidirectional"))
    )
    (net (code "53") (name "RN52_MIC_R+") (class "Default")
      (node (ref "R21") (pin "1") (pinfunction "1_1") (pintype "passive"))
      (node (ref "U4") (pin "33") (pinfunction "MIC_R+_33") (pintype "bidirectional"))
    )
    (net (code "54") (name "RN52_MIC_R-") (class "Default")
      (node (ref "R16") (pin "1") (pinfunction "1_1") (pintype "passive"))
      (node (ref "U4") (pin "35") (pinfunction "MIC_R-_35") (pintype "bidirectional"))
    )
    (net (code "55") (name "RN52_PWREN") (class "Default")
      (node (ref "U3") (pin "3") (pinfunction "RPC7/PMA0/RC7_3") (pintype "bidirectional"))
      (node (ref "U4") (pin "19") (pinfunction "PWREN_19") (pintype "bidirectional"))
    )
    (net (code "56") (name "RN52_SPKR_L+") (class "Default")
      (node (ref "R22") (pin "2") (pinfunction "2_2") (pintype "passive"))
      (node (ref "U4") (pin "40") (pinfunction "SPKR_L+_40") (pintype "bidirectional"))
    )
    (net (code "57") (name "RN52_SPKR_L-") (class "Default")
      (node (ref "R14") (pin "1") (pinfunction "1_1") (pintype "passive"))
      (node (ref "U4") (pin "38") (pinfunction "SPKR_L-_38") (pintype "bidirectional"))
    )
    (net (code "58") (name "RN52_SPKR_R+") (class "Default")
      (node (ref "TP3") (pin "TP") (pinfunction "TP_TP") (pintype "input"))
      (node (ref "U4") (pin "39") (pinfunction "SPKR_R+_39") (pintype "bidirectional"))
    )
    (net (code "59") (name "RN52_SPKR_R-") (class "Default")
      (node (ref "R15") (pin "1") (pinfunction "1_1") (pintype "passive"))
      (node (ref "U4") (pin "37") (pinfunction "SPKR_R-_37") (pintype "bidirectional"))
    )
    (net (code "60") (name "SST25_CE#") (class "Default")
      (node (ref "TP20") (pin "TP") (pinfunction "TP_TP") (pintype "input"))
      (node (ref "U3") (pin "10") (pinfunction "AN12/PMD0/RB12_10") (pintype "bidirectional"))
    )
    (net (code "61") (name "SST25_MISO") (class "Default")
      (node (ref "TP23") (pin "TP") (pinfunction "TP_TP") (pintype "input"))
      (node (ref "U3") (pin "27") (pinfunction "AN8/RPC2/PMA2/RC2_27") (pintype "bidirectional"))
    )
    (net (code "62") (name "SST25_MOSI") (class "Default")
      (node (ref "TP21") (pin "TP") (pinfunction "TP_TP") (pintype "input"))
      (node (ref "U3") (pin "11") (pinfunction "AN11/RPB13/CTPLS/PMRD/RB13_11") (pintype "bidirectional"))
    )
    (net (code "63") (name "SST25_SCK") (class "Default")
      (node (ref "TP22") (pin "TP") (pinfunction "TP_TP") (pintype "input"))
      (node (ref "U3") (pin "15") (pinfunction "AN9/C3INA/RPB15/SCK2/CTED6/PMCS1/RB15_15") (pintype "bidirectional"))
    )
    (net (code "64") (name "SW0") (class "Default")
      (node (ref "R8") (pin "2") (pinfunction "2_2") (pintype "passive"))
      (node (ref "SW1") (pin "2") (pinfunction "2_2") (pintype "bidirectional"))
      (node (ref "U3") (pin "41") (pinfunction "PGED3/RPB5/PMD7/RB5_41") (pintype "bidirectional"))
    )
    (net (code "65") (name "SW1") (class "Default")
      (node (ref "R9") (pin "2") (pinfunction "2_2") (pintype "passive"))
      (node (ref "SW2") (pin "2") (pinfunction "2_2") (pintype "bidirectional"))
      (node (ref "U3") (pin "42") (pinfunction "PGEC3/RPB6/PMD6/RB6_42") (pintype "bidirectional"))
    )
    (net (code "66") (name "SW2") (class "Default")
      (node (ref "R10") (pin "2") (pinfunction "2_2") (pintype "passive"))
      (node (ref "SW3") (pin "2") (pinfunction "2_2") (pintype "bidirectional"))
      (node (ref "U3") (pin "43") (pinfunction "RPB7/CTED3/PMD5/INT0/RB7_43") (pintype "bidirectional"))
    )
    (net (code "67") (name "SW3") (class "Default")
      (node (ref "U3") (pin "44") (pinfunction "RPB8/SCL1/CTED10/PMD4/RB8_44") (pintype "bidirectional"))
    )
    (net (code "68") (name "USB_DM") (class "Default")
      (node (ref "P2") (pin "2") (pinfunction "2_2") (pintype "input"))
      (node (ref "U4") (pin "11") (pinfunction "USBD-_11") (pintype "bidirectional"))
    )
    (net (code "69") (name "USB_DP") (class "Default")
      (node (ref "P2") (pin "3") (pinfunction "3_3") (pintype "input"))
      (node (ref "U4") (pin "12") (pinfunction "USBD+_12") (pintype "bidirectional"))
    )
    (net (code "70") (name "USB_VBUS") (class "Default")
      (node (ref "C5") (pin "1") (pinfunction "1_1") (pintype "passive"))
      (node (ref "P2") (pin "1") (pinfunction "1_1") (pintype "input"))
      (node (ref "R12") (pin "1") (pinfunction "1_1") (pintype "passive"))
      (node (ref "U1") (pin "2") (pinfunction "VIN_2") (pintype "power_in"))
      (node (ref "U1") (pin "3") (pinfunction "EN_3") (pintype "input"))
    )
    (net (code "71") (name "unconnected-(P1-LVP-Pad6)") (class "Default")
      (node (ref "P1") (pin "6") (pinfunction "LVP_6") (pintype "bidirectional"))
    )
    (net (code "72") (name "unconnected-(P2-Pad4)") (class "Default")
      (node (ref "P2") (pin "4") (pinfunction "4_4") (pintype "input"))
    )
    (net (code "73") (name "unconnected-(P3-Pad1)") (class "Default")
      (node (ref "P3") (pin "1") (pinfunction "1_1") (pintype "bidirectional"))
    )
    (net (code "74") (name "unconnected-(P3-Pad4)") (class "Default")
      (node (ref "P3") (pin "4") (pinfunction "4_4") (pintype "bidirectional"))
    )
    (net (code "75") (name "unconnected-(U2-ZB-Pad8)") (class "Default")
      (node (ref "U2") (pin "8") (pinfunction "ZB_8") (pintype "bidirectional"))
    )
    (net (code "76") (name "unconnected-(U2-ZT1-Pad6)") (class "Default")
      (node (ref "U2") (pin "6") (pinfunction "ZT1_6") (pintype "bidirectional"))
    )
    (net (code "77") (name "unconnected-(U2-ZT2-Pad7)") (class "Default")
      (node (ref "U2") (pin "7") (pinfunction "ZT2_7") (pintype "bidirectional"))
    )
    (net (code "78") (name "unconnected-(U4-AIC0-Pad3)") (class "Default")
      (node (ref "U4") (pin "3") (pinfunction "AIC0_3") (pintype "bidirectional"))
    )
    (net (code "79") (name "unconnected-(U4-GPIO5-Pad5)") (class "Default")
      (node (ref "U4") (pin "5") (pinfunction "GPIO5_5") (pintype "bidirectional"))
    )
    (net (code "80") (name "unconnected-(U4-GPIO6-Pad18)") (class "Default")
      (node (ref "U4") (pin "18") (pinfunction "GPIO6_18") (pintype "bidirectional"))
    )
    (net (code "81") (name "unconnected-(U4-GPIO7-Pad17)") (class "Default")
      (node (ref "U4") (pin "17") (pinfunction "GPIO7_17") (pintype "bidirectional"))
    )
    (net (code "82") (name "unconnected-(U4-GPIO10-Pad9)") (class "Default")
      (node (ref "U4") (pin "9") (pinfunction "GPIO10_9") (pintype "bidirectional"))
    )
    (net (code "83") (name "unconnected-(U4-GPIO11-Pad8)") (class "Default")
      (node (ref "U4") (pin "8") (pinfunction "GPIO11_8") (pintype "bidirectional"))
    )
    (net (code "84") (name "unconnected-(U4-GPIO12-Pad6)") (class "Default")
      (node (ref "U4") (pin "6") (pinfunction "GPIO12_6") (pintype "bidirectional"))
    )
    (net (code "85") (name "unconnected-(U4-GPIO13-Pad7)") (class "Default")
      (node (ref "U4") (pin "7") (pinfunction "GPIO13_7") (pintype "bidirectional"))
    )
    (net (code "86") (name "unconnected-(U4-PCM_CLK-Pad24)") (class "Default")
      (node (ref "U4") (pin "24") (pinfunction "PCM_CLK_24") (pintype "bidirectional"))
    )
    (net (code "87") (name "unconnected-(U4-PCM_IN-Pad21)") (class "Default")
      (node (ref "U4") (pin "21") (pinfunction "PCM_IN_21") (pintype "bidirectional"))
    )
    (net (code "88") (name "unconnected-(U4-PCM_OUT-Pad22)") (class "Default")
      (node (ref "U4") (pin "22") (pinfunction "PCM_OUT_22") (pintype "bidirectional"))
    )
    (net (code "89") (name "unconnected-(U4-PCM_SYNC-Pad23)") (class "Default")
      (node (ref "U4") (pin "23") (pinfunction "PCM_SYNC_23") (pintype "bidirectional"))
    )
    (net (code "90") (name "unconnected-(U4-SPI_CLK-Pad27)") (class "Default")
      (node (ref "U4") (pin "27") (pinfunction "SPI_CLK_27") (pintype "bidirectional"))
    )
    (net (code "91") (name "unconnected-(U4-SPI_MISO-Pad26)") (class "Default")
      (node (ref "U4") (pin "26") (pinfunction "SPI_MISO_26") (pintype "bidirectional"))
    )
    (net (code "92") (name "unconnected-(U4-SPI_MOSI-Pad28)") (class "Default")
      (node (ref "U4") (pin "28") (pinfunction "SPI_MOSI_28") (pintype "bidirectional"))
    )
    (net (code "93") (name "unconnected-(U4-SPI_SS-Pad25)") (class "Default")
      (node (ref "U4") (pin "25") (pinfunction "SPI_SS_25") (pintype "bidirectional"))
    )
  )
)
